# QED_2550_dos_caras.net
KiCad netlist of a schematic drawn in EAGLE
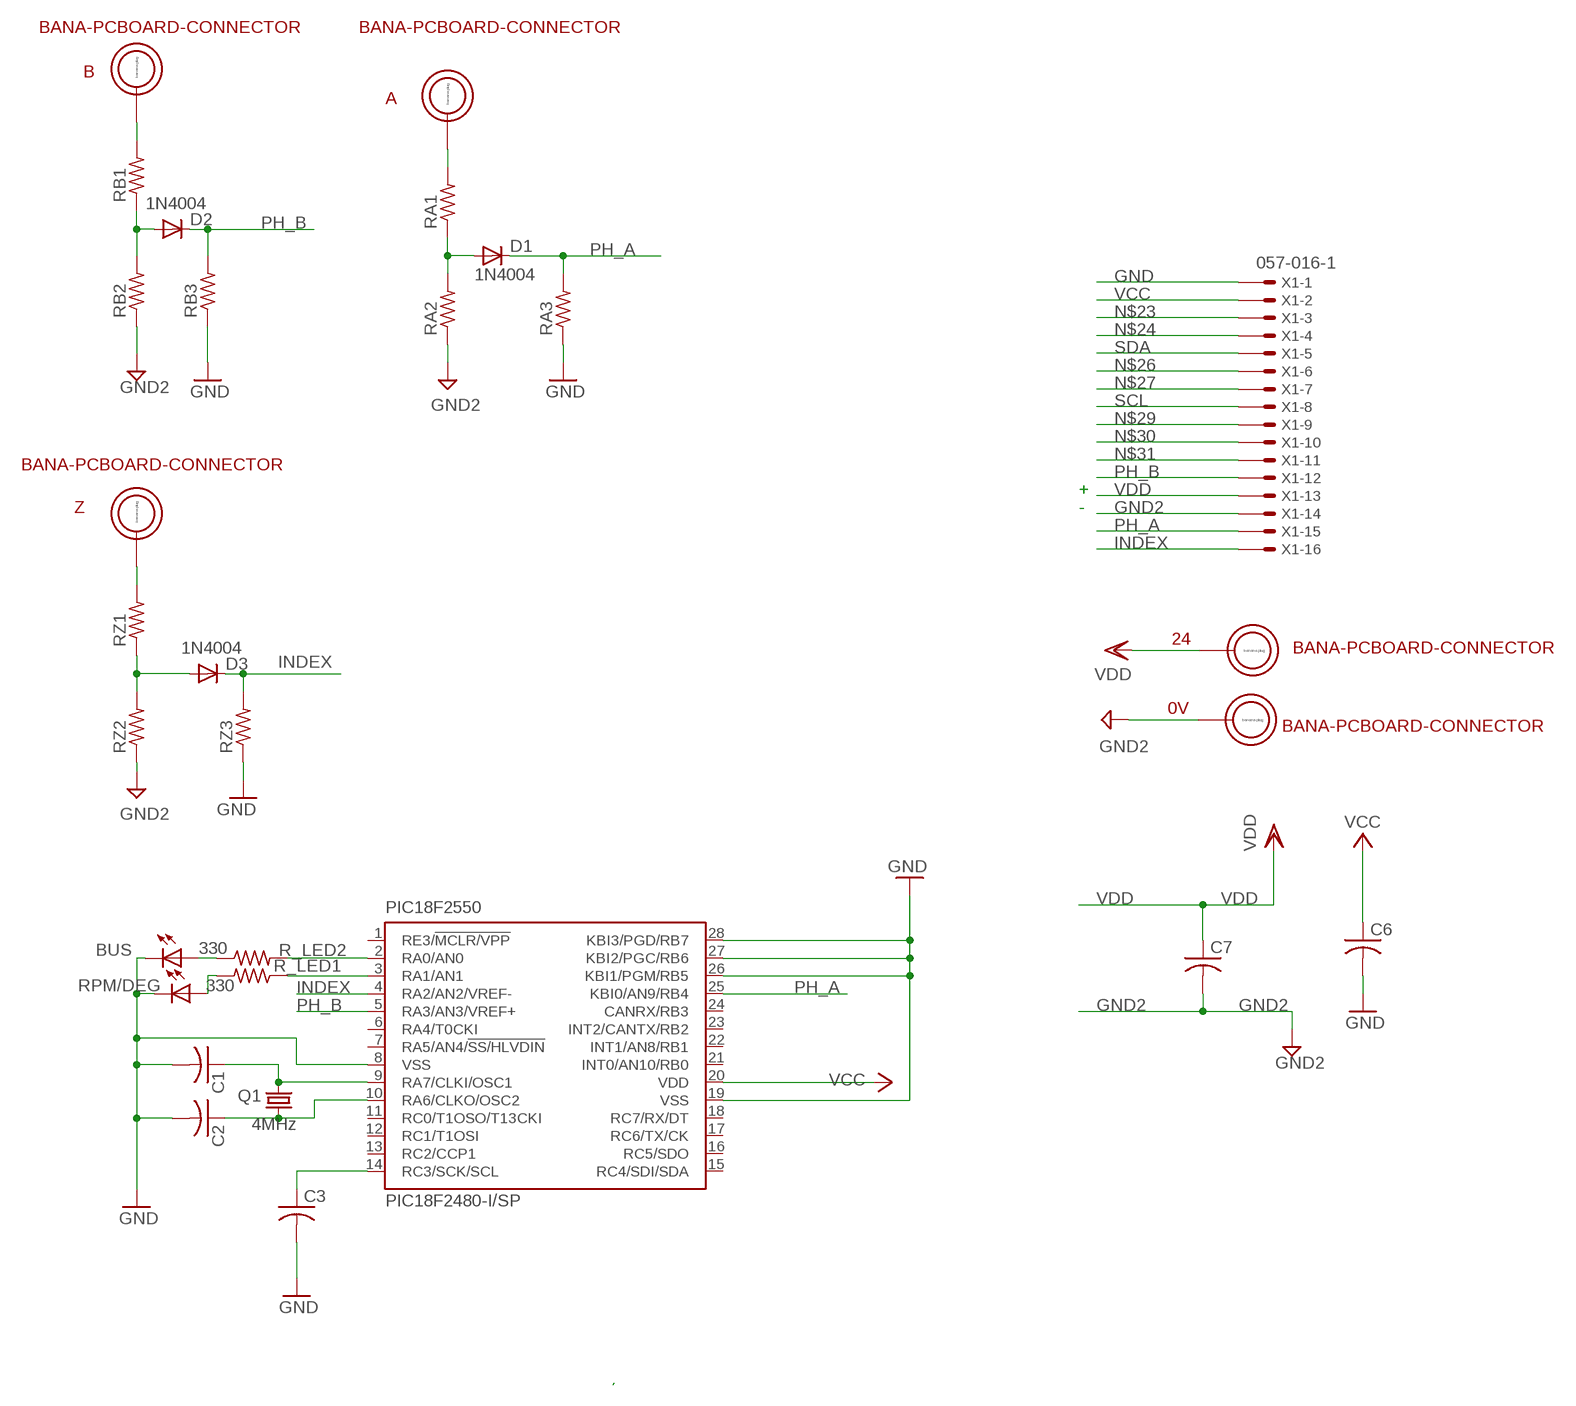
[diagram p0: schematic, sheet 1]

(export (version "E")
  (design (tool "Eeschema 10.0.6"))
  (components
    (comp (ref "0V")
      (value "BANA-PCBOARD-CONNECTOR")
      (footprint "eagle-import:BANA_PLUG")
      (libsource (lib "eagle-import") (part "BANA-PCBOARD-CONNECTOR"))
    )
    (comp (ref "24")
      (value "BANA-PCBOARD-CONNECTOR")
      (footprint "eagle-import:BANA_PLUG")
      (libsource (lib "eagle-import") (part "BANA-PCBOARD-CONNECTOR"))
    )
    (comp (ref "A")
      (value "BANA-PCBOARD-CONNECTOR")
      (footprint "eagle-import:BANA_PLUG")
      (libsource (lib "eagle-import") (part "BANA-PCBOARD-CONNECTOR"))
    )
    (comp (ref "B")
      (value "BANA-PCBOARD-CONNECTOR")
      (footprint "eagle-import:BANA_PLUG")
      (libsource (lib "eagle-import") (part "BANA-PCBOARD-CONNECTOR"))
    )
    (comp (ref "BUS")
      (value "LED5MM")
      (footprint "eagle-import:LED5MM")
      (libsource (lib "eagle-import") (part "LED5MM"))
    )
    (comp (ref "C1")
      (value "C-US025-024X044")
      (footprint "eagle-import:C025-024X044")
      (libsource (lib "eagle-import") (part "C-US025-024X044"))
    )
    (comp (ref "C2")
      (value "C-US025-024X044")
      (footprint "eagle-import:C025-024X044")
      (libsource (lib "eagle-import") (part "C-US025-024X044"))
    )
    (comp (ref "C3")
      (value "C-US025-024X044")
      (footprint "eagle-import:C025-024X044")
      (libsource (lib "eagle-import") (part "C-US025-024X044"))
    )
    (comp (ref "C6")
      (value "C-US025-030X050")
      (footprint "eagle-import:C025-030X050")
      (libsource (lib "eagle-import") (part "C-US025-030X050"))
    )
    (comp (ref "C7")
      (value "C-US025-030X050")
      (footprint "eagle-import:C025-030X050")
      (libsource (lib "eagle-import") (part "C-US025-030X050"))
    )
    (comp (ref "D1")
      (value "1N4004")
      (footprint "eagle-import:DO41-10")
      (libsource (lib "eagle-import") (part "1N4004"))
    )
    (comp (ref "D2")
      (value "1N4004")
      (footprint "eagle-import:DO41-10")
      (libsource (lib "eagle-import") (part "1N4004"))
    )
    (comp (ref "D3")
      (value "1N4004")
      (footprint "eagle-import:DO41-10")
      (libsource (lib "eagle-import") (part "1N4004"))
    )
    (comp (ref "PIC18F2550")
      (value "PIC18F2480-I/SP")
      (footprint "eagle-import:DIL28-3")
      (fields (field (name "MF") "MICROCHIP"))
      (libsource (lib "eagle-import") (part "PIC18F280-I/SP4"))
    )
    (comp (ref "Q1")
      (value "4MHz")
      (footprint "eagle-import:HC49_S")
      (libsource (lib "eagle-import") (part "CRYSTALHC49S"))
    )
    (comp (ref "RA1")
      (value "R-US_0204/7")
      (footprint "eagle-import:0204_7")
      (libsource (lib "eagle-import") (part "R-US_0204/7"))
    )
    (comp (ref "RA2")
      (value "R-US_0204/7")
      (footprint "eagle-import:0204_7")
      (libsource (lib "eagle-import") (part "R-US_0204/7"))
    )
    (comp (ref "RA3")
      (value "R-US_0204/7")
      (footprint "eagle-import:0204_7")
      (libsource (lib "eagle-import") (part "R-US_0204/7"))
    )
    (comp (ref "RB1")
      (value "R-US_0204/7")
      (footprint "eagle-import:0204_7")
      (libsource (lib "eagle-import") (part "R-US_0204/7"))
    )
    (comp (ref "RB2")
      (value "R-US_0204/7")
      (footprint "eagle-import:0204_7")
      (libsource (lib "eagle-import") (part "R-US_0204/7"))
    )
    (comp (ref "RB3")
      (value "R-US_0204/7")
      (footprint "eagle-import:0204_7")
      (libsource (lib "eagle-import") (part "R-US_0204/7"))
    )
    (comp (ref "RPM/DEG")
      (value "LED5MM")
      (footprint "eagle-import:LED5MM")
      (libsource (lib "eagle-import") (part "LED5MM"))
    )
    (comp (ref "RZ1")
      (value "R-US_0204/7")
      (footprint "eagle-import:0204_7")
      (libsource (lib "eagle-import") (part "R-US_0204/7"))
    )
    (comp (ref "RZ2")
      (value "R-US_0204/7")
      (footprint "eagle-import:0204_7")
      (libsource (lib "eagle-import") (part "R-US_0204/7"))
    )
    (comp (ref "RZ3")
      (value "R-US_0204/7")
      (footprint "eagle-import:0204_7")
      (libsource (lib "eagle-import") (part "R-US_0204/7"))
    )
    (comp (ref "R_LED1")
      (value "330")
      (footprint "eagle-import:0204_7")
      (libsource (lib "eagle-import") (part "R-US_0204/7"))
    )
    (comp (ref "R_LED2")
      (value "330")
      (footprint "eagle-import:0204_7")
      (libsource (lib "eagle-import") (part "R-US_0204/7"))
    )
    (comp (ref "X1")
      (value "057-016-1")
      (footprint "eagle-import:057-016-1")
      (libsource (lib "eagle-import") (part "057-016-1"))
    )
    (comp (ref "Z")
      (value "BANA-PCBOARD-CONNECTOR")
      (footprint "eagle-import:BANA_PLUG")
      (libsource (lib "eagle-import") (part "BANA-PCBOARD-CONNECTOR"))
    )
  )
  (nets
    (net (code "1") (name "/INDEX") (class "Default")
      (node (ref "D3") (pin "C") (pinfunction "C_C") (pintype "passive"))
      (node (ref "PIC18F2550") (pin "4") (pinfunction "RA2/AN2/VREF-_4") (pintype "bidirectional"))
      (node (ref "RZ3") (pin "2") (pinfunction "2_2") (pintype "passive"))
      (node (ref "X1") (pin "16") (pinfunction "S_16") (pintype "passive"))
    )
    (net (code "2") (name "/N$23") (class "Default")
      (node (ref "X1") (pin "3") (pinfunction "S_3") (pintype "passive"))
    )
    (net (code "3") (name "/N$24") (class "Default")
      (node (ref "X1") (pin "4") (pinfunction "S_4") (pintype "passive"))
    )
    (net (code "4") (name "/N$26") (class "Default")
      (node (ref "X1") (pin "6") (pinfunction "S_6") (pintype "passive"))
    )
    (net (code "5") (name "/N$27") (class "Default")
      (node (ref "X1") (pin "7") (pinfunction "S_7") (pintype "passive"))
    )
    (net (code "6") (name "/N$29") (class "Default")
      (node (ref "X1") (pin "9") (pinfunction "S_9") (pintype "passive"))
    )
    (net (code "7") (name "/N$30") (class "Default")
      (node (ref "X1") (pin "10") (pinfunction "S_10") (pintype "passive"))
    )
    (net (code "8") (name "/N$31") (class "Default")
      (node (ref "X1") (pin "11") (pinfunction "S_11") (pintype "passive"))
    )
    (net (code "9") (name "/PH_A") (class "Default")
      (node (ref "D1") (pin "C") (pinfunction "C_C") (pintype "passive"))
      (node (ref "PIC18F2550") (pin "25") (pinfunction "KBI0/AN9/RB4_25") (pintype "bidirectional"))
      (node (ref "RA3") (pin "2") (pinfunction "2_2") (pintype "passive"))
      (node (ref "X1") (pin "15") (pinfunction "S_15") (pintype "passive"))
    )
    (net (code "10") (name "/PH_B") (class "Default")
      (node (ref "D2") (pin "C") (pinfunction "C_C") (pintype "passive"))
      (node (ref "PIC18F2550") (pin "5") (pinfunction "RA3/AN3/VREF+_5") (pintype "bidirectional"))
      (node (ref "RB3") (pin "2") (pinfunction "2_2") (pintype "passive"))
      (node (ref "X1") (pin "12") (pinfunction "S_12") (pintype "passive"))
    )
    (net (code "11") (name "/SCL") (class "Default")
      (node (ref "X1") (pin "8") (pinfunction "S_8") (pintype "passive"))
    )
    (net (code "12") (name "/SDA") (class "Default")
      (node (ref "X1") (pin "5") (pinfunction "S_5") (pintype "passive"))
    )
    (net (code "13") (name "GND") (class "Default")
      (node (ref "BUS") (pin "K") (pinfunction "C_K") (pintype "passive"))
      (node (ref "C1") (pin "2") (pinfunction "2_2") (pintype "passive"))
      (node (ref "C2") (pin "2") (pinfunction "2_2") (pintype "passive"))
      (node (ref "C3") (pin "2") (pinfunction "2_2") (pintype "passive"))
      (node (ref "C6") (pin "2") (pinfunction "2_2") (pintype "passive"))
      (node (ref "PIC18F2550") (pin "19") (pinfunction "VSS_19") (pintype "power_in"))
      (node (ref "PIC18F2550") (pin "26") (pinfunction "KBI1/PGM/RB5_26") (pintype "bidirectional"))
      (node (ref "PIC18F2550") (pin "27") (pinfunction "KBI2/PGC/RB6_27") (pintype "bidirectional"))
      (node (ref "PIC18F2550") (pin "28") (pinfunction "KBI3/PGD/RB7_28") (pintype "bidirectional"))
      (node (ref "PIC18F2550") (pin "8") (pinfunction "VSS_8") (pintype "power_in"))
      (node (ref "RA3") (pin "1") (pinfunction "1_1") (pintype "passive"))
      (node (ref "RB3") (pin "1") (pinfunction "1_1") (pintype "passive"))
      (node (ref "RPM/DEG") (pin "K") (pinfunction "C_K") (pintype "passive"))
      (node (ref "RZ3") (pin "1") (pinfunction "1_1") (pintype "passive"))
      (node (ref "X1") (pin "1") (pinfunction "S_1") (pintype "passive"))
    )
    (net (code "14") (name "GND2") (class "Default")
      (node (ref "0V") (pin "P$1") (pinfunction "P$1_P$1") (pintype "bidirectional"))
      (node (ref "C7") (pin "2") (pinfunction "2_2") (pintype "passive"))
      (node (ref "RA2") (pin "1") (pinfunction "1_1") (pintype "passive"))
      (node (ref "RB2") (pin "1") (pinfunction "1_1") (pintype "passive"))
      (node (ref "RZ2") (pin "1") (pinfunction "1_1") (pintype "passive"))
      (node (ref "X1") (pin "14") (pinfunction "S_14") (pintype "passive"))
    )
    (net (code "15") (name "Net-(A-PadP$1)") (class "Default")
      (node (ref "A") (pin "P$1") (pinfunction "P$1_P$1") (pintype "bidirectional"))
      (node (ref "RA1") (pin "2") (pinfunction "2_2") (pintype "passive"))
    )
    (net (code "16") (name "Net-(B-PadP$1)") (class "Default")
      (node (ref "B") (pin "P$1") (pinfunction "P$1_P$1") (pintype "bidirectional"))
      (node (ref "RB1") (pin "2") (pinfunction "2_2") (pintype "passive"))
    )
    (net (code "17") (name "Net-(BUS-PadA)") (class "Default")
      (node (ref "BUS") (pin "A") (pinfunction "A_A") (pintype "passive"))
      (node (ref "R_LED2") (pin "1") (pinfunction "1_1") (pintype "passive"))
    )
    (net (code "18") (name "Net-(D1-PadA)") (class "Default")
      (node (ref "D1") (pin "A") (pinfunction "A_A") (pintype "passive"))
      (node (ref "RA1") (pin "1") (pinfunction "1_1") (pintype "passive"))
      (node (ref "RA2") (pin "2") (pinfunction "2_2") (pintype "passive"))
    )
    (net (code "19") (name "Net-(D2-PadA)") (class "Default")
      (node (ref "D2") (pin "A") (pinfunction "A_A") (pintype "passive"))
      (node (ref "RB1") (pin "1") (pinfunction "1_1") (pintype "passive"))
      (node (ref "RB2") (pin "2") (pinfunction "2_2") (pintype "passive"))
    )
    (net (code "20") (name "Net-(D3-PadA)") (class "Default")
      (node (ref "D3") (pin "A") (pinfunction "A_A") (pintype "passive"))
      (node (ref "RZ1") (pin "1") (pinfunction "1_1") (pintype "passive"))
      (node (ref "RZ2") (pin "2") (pinfunction "2_2") (pintype "passive"))
    )
    (net (code "21") (name "Net-(PIC18F2550-RA0{slash}AN0)") (class "Default")
      (node (ref "PIC18F2550") (pin "2") (pinfunction "RA0/AN0_2") (pintype "bidirectional"))
      (node (ref "R_LED2") (pin "2") (pinfunction "2_2") (pintype "passive"))
    )
    (net (code "22") (name "Net-(PIC18F2550-RA1{slash}AN1)") (class "Default")
      (node (ref "PIC18F2550") (pin "3") (pinfunction "RA1/AN1_3") (pintype "bidirectional"))
      (node (ref "R_LED1") (pin "1") (pinfunction "1_1") (pintype "passive"))
    )
    (net (code "23") (name "Net-(PIC18F2550-RA6{slash}CLKO{slash}OSC2)") (class "Default")
      (node (ref "C2") (pin "1") (pinfunction "1_1") (pintype "passive"))
      (node (ref "PIC18F2550") (pin "10") (pinfunction "RA6/CLKO/OSC2_10") (pintype "output"))
      (node (ref "Q1") (pin "1") (pinfunction "1_1") (pintype "passive"))
    )
    (net (code "24") (name "Net-(PIC18F2550-RA7{slash}CLKI{slash}OSC1)") (class "Default")
      (node (ref "C1") (pin "1") (pinfunction "1_1") (pintype "passive"))
      (node (ref "PIC18F2550") (pin "9") (pinfunction "RA7/CLKI/OSC1_9") (pintype "input"))
      (node (ref "Q1") (pin "2") (pinfunction "2_2") (pintype "passive"))
    )
    (net (code "25") (name "Net-(PIC18F2550-RC3{slash}SCK{slash}SCL)") (class "Default")
      (node (ref "C3") (pin "1") (pinfunction "1_1") (pintype "passive"))
      (node (ref "PIC18F2550") (pin "14") (pinfunction "RC3/SCK/SCL_14") (pintype "bidirectional"))
    )
    (net (code "26") (name "Net-(RPM/DEG-PadA)") (class "Default")
      (node (ref "RPM/DEG") (pin "A") (pinfunction "A_A") (pintype "passive"))
      (node (ref "R_LED1") (pin "2") (pinfunction "2_2") (pintype "passive"))
    )
    (net (code "27") (name "Net-(RZ1-Pad2)") (class "Default")
      (node (ref "RZ1") (pin "2") (pinfunction "2_2") (pintype "passive"))
      (node (ref "Z") (pin "P$1") (pinfunction "P$1_P$1") (pintype "bidirectional"))
    )
    (net (code "28") (name "VCC") (class "Default")
      (node (ref "C6") (pin "1") (pinfunction "1_1") (pintype "passive"))
      (node (ref "PIC18F2550") (pin "20") (pinfunction "VDD_20") (pintype "power_in"))
      (node (ref "X1") (pin "2") (pinfunction "S_2") (pintype "passive"))
    )
    (net (code "29") (name "VDD") (class "Default")
      (node (ref "24") (pin "P$1") (pinfunction "P$1_P$1") (pintype "bidirectional"))
      (node (ref "C7") (pin "1") (pinfunction "1_1") (pintype "passive"))
      (node (ref "X1") (pin "13") (pinfunction "S_13") (pintype "passive"))
    )
    (net (code "30") (name "unconnected-(PIC18F2550-CANRX{slash}RB3-Pad24)") (class "Default")
      (node (ref "PIC18F2550") (pin "24") (pinfunction "CANRX/RB3_24") (pintype "bidirectional"))
    )
    (net (code "31") (name "unconnected-(PIC18F2550-INT0{slash}AN10{slash}RB0-Pad21)") (class "Default")
      (node (ref "PIC18F2550") (pin "21") (pinfunction "INT0/AN10/RB0_21") (pintype "bidirectional"))
    )
    (net (code "32") (name "unconnected-(PIC18F2550-INT1{slash}AN8{slash}RB1-Pad22)") (class "Default")
      (node (ref "PIC18F2550") (pin "22") (pinfunction "INT1/AN8/RB1_22") (pintype "bidirectional"))
    )
    (net (code "33") (name "unconnected-(PIC18F2550-INT2{slash}CANTX{slash}RB2-Pad23)") (class "Default")
      (node (ref "PIC18F2550") (pin "23") (pinfunction "INT2/CANTX/RB2_23") (pintype "bidirectional"))
    )
    (net (code "34") (name "unconnected-(PIC18F2550-RA4{slash}T0CKI-Pad6)") (class "Default")
      (node (ref "PIC18F2550") (pin "6") (pinfunction "RA4/T0CKI_6") (pintype "bidirectional"))
    )
    (net (code "35") (name "unconnected-(PIC18F2550-RA5{slash}AN4{slash}~{SS{slash}HLVDIN}-Pad7)") (class "Default")
      (node (ref "PIC18F2550") (pin "7") (pinfunction "RA5/AN4/~{SS/HLVDIN}_7") (pintype "bidirectional"))
    )
    (net (code "36") (name "unconnected-(PIC18F2550-RC0{slash}T1OSO{slash}T13CKI-Pad11)") (class "Default")
      (node (ref "PIC18F2550") (pin "11") (pinfunction "RC0/T1OSO/T13CKI_11") (pintype "bidirectional"))
    )
    (net (code "37") (name "unconnected-(PIC18F2550-RC1{slash}T1OSI-Pad12)") (class "Default")
      (node (ref "PIC18F2550") (pin "12") (pinfunction "RC1/T1OSI_12") (pintype "bidirectional"))
    )
    (net (code "38") (name "unconnected-(PIC18F2550-RC2{slash}CCP1-Pad13)") (class "Default")
      (node (ref "PIC18F2550") (pin "13") (pinfunction "RC2/CCP1_13") (pintype "bidirectional"))
    )
    (net (code "39") (name "unconnected-(PIC18F2550-RC4{slash}SDI{slash}SDA-Pad15)") (class "Default")
      (node (ref "PIC18F2550") (pin "15") (pinfunction "RC4/SDI/SDA_15") (pintype "bidirectional"))
    )
    (net (code "40") (name "unconnected-(PIC18F2550-RC5{slash}SDO-Pad16)") (class "Default")
      (node (ref "PIC18F2550") (pin "16") (pinfunction "RC5/SDO_16") (pintype "bidirectional"))
    )
    (net (code "41") (name "unconnected-(PIC18F2550-RC6{slash}TX{slash}CK-Pad17)") (class "Default")
      (node (ref "PIC18F2550") (pin "17") (pinfunction "RC6/TX/CK_17") (pintype "bidirectional"))
    )
    (net (code "42") (name "unconnected-(PIC18F2550-RC7{slash}RX{slash}DT-Pad18)") (class "Default")
      (node (ref "PIC18F2550") (pin "18") (pinfunction "RC7/RX/DT_18") (pintype "bidirectional"))
    )
    (net (code "43") (name "unconnected-(PIC18F2550-RE3{slash}~{MCLR{slash}VPP}-Pad1)") (class "Default")
      (node (ref "PIC18F2550") (pin "1") (pinfunction "RE3/~{MCLR/VPP}_1") (pintype "input"))
    )
  )
)
